# Pico_Audio_v0_10.net
KiCad netlist of a schematic drawn in EAGLE
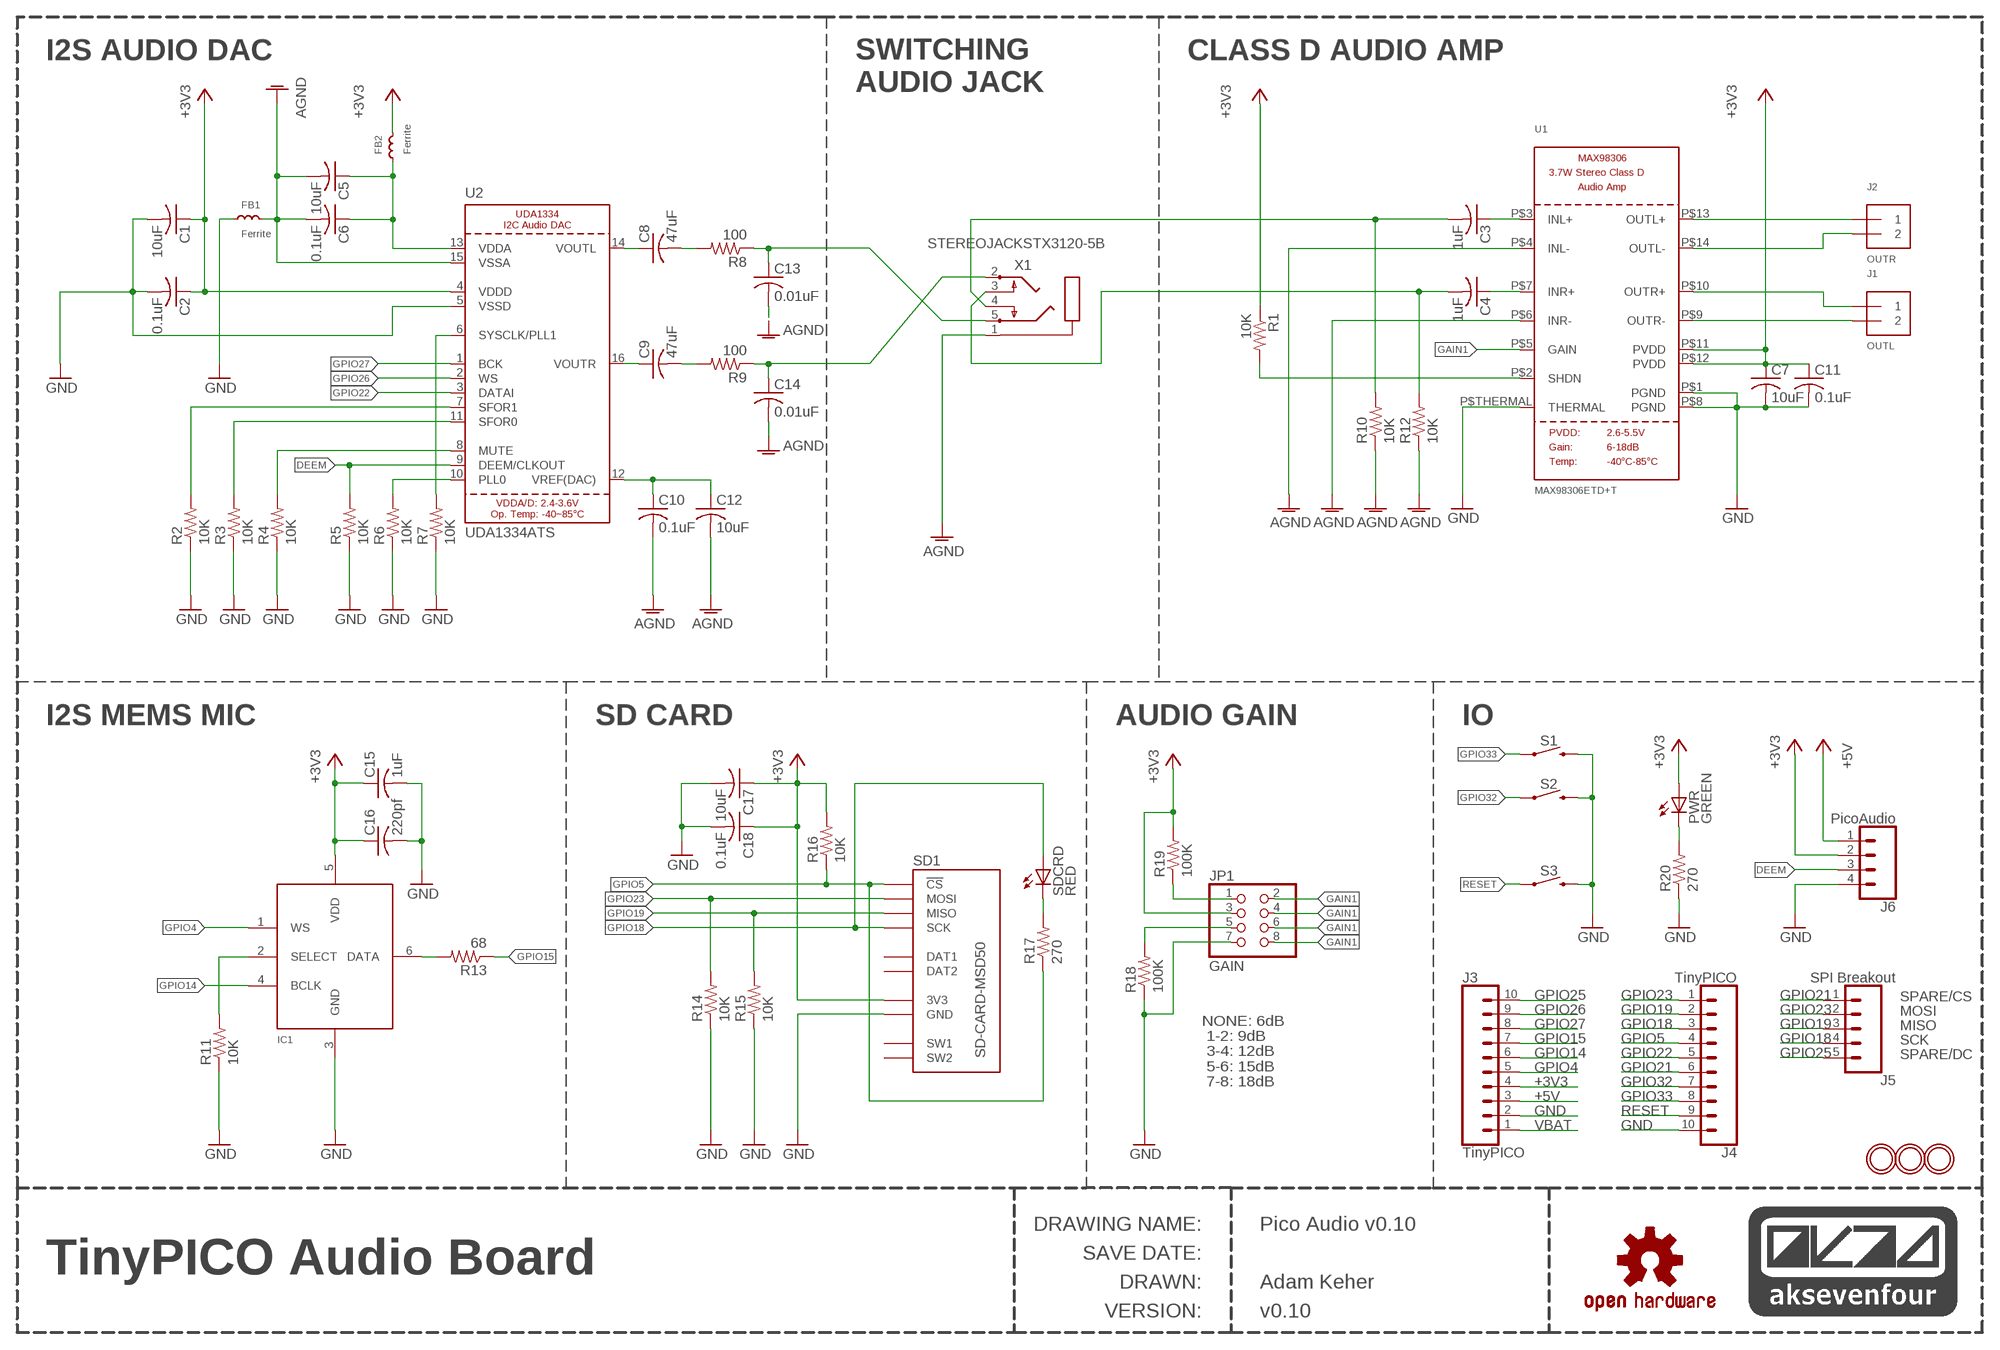
[diagram p0: schematic, sheet 1]

(export (version "E")
  (design (tool "Eeschema 10.0.6"))
  (components
    (comp (ref "AK74LOGO2")
      (value "AK74_LOGO")
      (footprint "eagle-import:AK74_LOGO_MEDIUM_TEXTONLY")
      (libsource (lib "eagle-import") (part "AK74_LOGO"))
    )
    (comp (ref "C1")
      (value "10uF")
      (footprint "eagle-import:C0603K")
      (libsource (lib "eagle-import") (part "C-USC0603K"))
    )
    (comp (ref "C2")
      (value "0.1uF")
      (footprint "eagle-import:C0402K")
      (libsource (lib "eagle-import") (part "C-USC0402K"))
    )
    (comp (ref "C3")
      (value "1uF")
      (footprint "eagle-import:C0402K")
      (libsource (lib "eagle-import") (part "C-USC0402K"))
    )
    (comp (ref "C4")
      (value "1uF")
      (footprint "eagle-import:C0402K")
      (libsource (lib "eagle-import") (part "C-USC0402K"))
    )
    (comp (ref "C5")
      (value "10uF")
      (footprint "eagle-import:C0603K")
      (libsource (lib "eagle-import") (part "C-USC0603K"))
    )
    (comp (ref "C6")
      (value "0.1uF")
      (footprint "eagle-import:C0402K")
      (libsource (lib "eagle-import") (part "C-USC0402K"))
    )
    (comp (ref "C7")
      (value "10uF")
      (footprint "eagle-import:C0603K")
      (libsource (lib "eagle-import") (part "C-USC0603K"))
    )
    (comp (ref "C8")
      (value "47uF")
      (footprint "eagle-import:C1210K")
      (libsource (lib "eagle-import") (part "C-USC1210K"))
    )
    (comp (ref "C9")
      (value "47uF")
      (footprint "eagle-import:C1210K")
      (libsource (lib "eagle-import") (part "C-USC1210K"))
    )
    (comp (ref "C10")
      (value "0.1uF")
      (footprint "eagle-import:C0402K")
      (libsource (lib "eagle-import") (part "C-USC0402K"))
    )
    (comp (ref "C11")
      (value "0.1uF")
      (footprint "eagle-import:C0402K")
      (libsource (lib "eagle-import") (part "C-USC0402K"))
    )
    (comp (ref "C12")
      (value "10uF")
      (footprint "eagle-import:C0603K")
      (libsource (lib "eagle-import") (part "C-USC0603K"))
    )
    (comp (ref "C13")
      (value "0.01uF")
      (footprint "eagle-import:C0402K")
      (libsource (lib "eagle-import") (part "C-USC0402K"))
    )
    (comp (ref "C14")
      (value "0.01uF")
      (footprint "eagle-import:C0402K")
      (libsource (lib "eagle-import") (part "C-USC0402K"))
    )
    (comp (ref "C15")
      (value "1uF")
      (footprint "eagle-import:C0402K")
      (libsource (lib "eagle-import") (part "C-USC0402K"))
    )
    (comp (ref "C16")
      (value "220pf")
      (footprint "eagle-import:C0402K")
      (libsource (lib "eagle-import") (part "C-USC0402K"))
    )
    (comp (ref "C17")
      (value "10uF")
      (footprint "eagle-import:C0603K")
      (libsource (lib "eagle-import") (part "C-USC0603K"))
    )
    (comp (ref "C18")
      (value "0.1uF")
      (footprint "eagle-import:C0402K")
      (libsource (lib "eagle-import") (part "C-USC0402K"))
    )
    (comp (ref "FB1")
      (value "Ferrite")
      (footprint "eagle-import:R0805")
      (libsource (lib "eagle-import") (part "FERRITEL0805"))
    )
    (comp (ref "FB2")
      (value "Ferrite")
      (footprint "eagle-import:R0805")
      (libsource (lib "eagle-import") (part "FERRITEL0805"))
    )
    (comp (ref "IC1")
      (value "MIC_I2S_SPH0645")
      (footprint "eagle-import:SPH0645LM4H")
      (libsource (lib "eagle-import") (part "MIC_I2S_SPH0645"))
    )
    (comp (ref "J1")
      (value "OUTL")
      (footprint "eagle-import:TERMBLOCK_1X2-3.5MM")
      (libsource (lib "eagle-import") (part "TERMBLOCK_1X2"))
    )
    (comp (ref "J2")
      (value "OUTR")
      (footprint "eagle-import:TERMBLOCK_1X2-3.5MM")
      (libsource (lib "eagle-import") (part "TERMBLOCK_1X2"))
    )
    (comp (ref "J3")
      (value "TinyPICO")
      (footprint "eagle-import:1X10_NO_SILK")
      (libsource (lib "eagle-import") (part "TINYPICO_HEADER_10NO_SILK_PTH_FEMALE"))
    )
    (comp (ref "J4")
      (value "TinyPICO")
      (footprint "eagle-import:1X10_NO_SILK")
      (libsource (lib "eagle-import") (part "TINYPICO_HEADER_10NO_SILK_PTH_FEMALE"))
    )
    (comp (ref "J5")
      (value "SPI Breakout")
      (footprint "eagle-import:1X05_NO_SILK")
      (libsource (lib "eagle-import") (part "CONN_05NO_SILK"))
    )
    (comp (ref "J6")
      (value "PicoAudio")
      (footprint "eagle-import:1X04_NO_SILK")
      (libsource (lib "eagle-import") (part "CONN_041X04_NO_SILK"))
    )
    (comp (ref "JP1")
      (value "GAIN")
      (footprint "eagle-import:2X04")
      (libsource (lib "eagle-import") (part "PINHD-2X4"))
    )
    (comp (ref "LOGO2")
      (value "OSHW-LOGOM")
      (footprint "eagle-import:OSHW-LOGO-M")
      (libsource (lib "eagle-import") (part "OSHW-LOGOM"))
    )
    (comp (ref "PWR")
      (value "GREEN")
      (footprint "eagle-import:CHIP-LED0805")
      (libsource (lib "eagle-import") (part "LEDCHIP-LED0805"))
    )
    (comp (ref "R1")
      (value "10K")
      (footprint "eagle-import:R0402")
      (libsource (lib "eagle-import") (part "R-US_R0402"))
    )
    (comp (ref "R2")
      (value "10K")
      (footprint "eagle-import:R0402")
      (libsource (lib "eagle-import") (part "R-US_R0402"))
    )
    (comp (ref "R3")
      (value "10K")
      (footprint "eagle-import:R0402")
      (libsource (lib "eagle-import") (part "R-US_R0402"))
    )
    (comp (ref "R4")
      (value "10K")
      (footprint "eagle-import:R0402")
      (libsource (lib "eagle-import") (part "R-US_R0402"))
    )
    (comp (ref "R5")
      (value "10K")
      (footprint "eagle-import:R0402")
      (libsource (lib "eagle-import") (part "R-US_R0402"))
    )
    (comp (ref "R6")
      (value "10K")
      (footprint "eagle-import:R0402")
      (libsource (lib "eagle-import") (part "R-US_R0402"))
    )
    (comp (ref "R7")
      (value "10K")
      (footprint "eagle-import:R0402")
      (libsource (lib "eagle-import") (part "R-US_R0402"))
    )
    (comp (ref "R8")
      (value "100")
      (footprint "eagle-import:R0402")
      (libsource (lib "eagle-import") (part "R-US_R0402"))
    )
    (comp (ref "R9")
      (value "100")
      (footprint "eagle-import:R0402")
      (libsource (lib "eagle-import") (part "R-US_R0402"))
    )
    (comp (ref "R10")
      (value "10K")
      (footprint "eagle-import:R0402")
      (libsource (lib "eagle-import") (part "R-US_R0402"))
    )
    (comp (ref "R11")
      (value "10K")
      (footprint "eagle-import:R0402")
      (libsource (lib "eagle-import") (part "R-US_R0402"))
    )
    (comp (ref "R12")
      (value "10K")
      (footprint "eagle-import:R0402")
      (libsource (lib "eagle-import") (part "R-US_R0402"))
    )
    (comp (ref "R13")
      (value "68")
      (footprint "eagle-import:R0402")
      (libsource (lib "eagle-import") (part "R-US_R0402"))
    )
    (comp (ref "R14")
      (value "10K")
      (footprint "eagle-import:R0402")
      (libsource (lib "eagle-import") (part "R-US_R0402"))
    )
    (comp (ref "R15")
      (value "10K")
      (footprint "eagle-import:R0402")
      (libsource (lib "eagle-import") (part "R-US_R0402"))
    )
    (comp (ref "R16")
      (value "10K")
      (footprint "eagle-import:R0402")
      (libsource (lib "eagle-import") (part "R-US_R0402"))
    )
    (comp (ref "R17")
      (value "270")
      (footprint "eagle-import:R0402")
      (libsource (lib "eagle-import") (part "R-US_R0402"))
    )
    (comp (ref "R18")
      (value "100K")
      (footprint "eagle-import:R0402")
      (libsource (lib "eagle-import") (part "R-US_R0402"))
    )
    (comp (ref "R19")
      (value "100K")
      (footprint "eagle-import:R0402")
      (libsource (lib "eagle-import") (part "R-US_R0402"))
    )
    (comp (ref "R20")
      (value "270")
      (footprint "eagle-import:R0402")
      (libsource (lib "eagle-import") (part "R-US_R0402"))
    )
    (comp (ref "S1")
      (value "MOMENTARY-SWITCH-SPST-SMD-4.6X2.8MM")
      (footprint "eagle-import:TACTILE_SWITCH_SMD_4.6X2.8MM")
      (libsource (lib "eagle-import") (part "MOMENTARY-SWITCH-SPST-SMD-4.6X2.8MM"))
    )
    (comp (ref "S2")
      (value "MOMENTARY-SWITCH-SPST-SMD-4.6X2.8MM")
      (footprint "eagle-import:TACTILE_SWITCH_SMD_4.6X2.8MM")
      (libsource (lib "eagle-import") (part "MOMENTARY-SWITCH-SPST-SMD-4.6X2.8MM"))
    )
    (comp (ref "S3")
      (value "MOMENTARY-SWITCH-SPST-SMD-4.6X2.8MM")
      (footprint "eagle-import:TACTILE_SWITCH_SMD_4.6X2.8MM")
      (libsource (lib "eagle-import") (part "MOMENTARY-SWITCH-SPST-SMD-4.6X2.8MM"))
    )
    (comp (ref "SD1")
      (value "SD-CARD-MSD50")
      (footprint "eagle-import:SD_5031821853")
      (libsource (lib "eagle-import") (part "SD-CARD-MSD50"))
    )
    (comp (ref "SDCRD")
      (value "RED")
      (footprint "eagle-import:CHIP-LED0805")
      (libsource (lib "eagle-import") (part "LEDCHIP-LED0805"))
    )
    (comp (ref "U$12")
      (value "MOUNTINGHOLE2.5")
      (footprint "eagle-import:MOUNTINGHOLE_2.5_PLATED")
      (libsource (lib "eagle-import") (part "MOUNTINGHOLE2.5"))
    )
    (comp (ref "U$13")
      (value "MOUNTINGHOLE2.5")
      (footprint "eagle-import:MOUNTINGHOLE_2.5_PLATED")
      (libsource (lib "eagle-import") (part "MOUNTINGHOLE2.5"))
    )
    (comp (ref "U$14")
      (value "MOUNTINGHOLE2.5")
      (footprint "eagle-import:MOUNTINGHOLE_2.5_PLATED")
      (libsource (lib "eagle-import") (part "MOUNTINGHOLE2.5"))
    )
    (comp (ref "U1")
      (value "MAX98306ETD+T")
      (footprint "eagle-import:TDFN14_3X3MM")
      (libsource (lib "eagle-import") (part "AUDIOAMP_MAX98306"))
    )
    (comp (ref "U2")
      (value "UDA1334ATS")
      (footprint "eagle-import:SSOP16_4.4MM")
      (libsource (lib "eagle-import") (part "AUDIO_I2S_UDA1334{dblquote}{dblquote}"))
    )
    (comp (ref "X1")
      (value "STEREOJACKSTX3120-5B")
      (footprint "eagle-import:STX3100")
      (libsource (lib "eagle-import") (part "STEREOJACKSTX3120-5B"))
    )
  )
  (nets
    (net (code "1") (name "+3V3") (class "Default")
      (node (ref "C1") (pin "1") (pinfunction "1_1") (pintype "passive"))
      (node (ref "C11") (pin "1") (pinfunction "1_1") (pintype "passive"))
      (node (ref "C15") (pin "1") (pinfunction "1_1") (pintype "passive"))
      (node (ref "C16") (pin "1") (pinfunction "1_1") (pintype "passive"))
      (node (ref "C17") (pin "1") (pinfunction "1_1") (pintype "passive"))
      (node (ref "C18") (pin "1") (pinfunction "1_1") (pintype "passive"))
      (node (ref "C2") (pin "1") (pinfunction "1_1") (pintype "passive"))
      (node (ref "C7") (pin "1") (pinfunction "1_1") (pintype "passive"))
      (node (ref "FB2") (pin "2") (pinfunction "2_2") (pintype "passive"))
      (node (ref "IC1") (pin "5") (pinfunction "VDD_5") (pintype "power_in"))
      (node (ref "J3") (pin "4") (pinfunction "4_4") (pintype "passive"))
      (node (ref "J6") (pin "2") (pinfunction "2_2") (pintype "passive"))
      (node (ref "JP1") (pin "3") (pinfunction "3_3") (pintype "passive"))
      (node (ref "PWR") (pin "A") (pinfunction "A_A") (pintype "passive"))
      (node (ref "R1") (pin "1") (pinfunction "1_1") (pintype "passive"))
      (node (ref "R16") (pin "2") (pinfunction "2_2") (pintype "passive"))
      (node (ref "R19") (pin "2") (pinfunction "2_2") (pintype "passive"))
      (node (ref "SD1") (pin "VCC") (pinfunction "3V3_VCC") (pintype "bidirectional"))
      (node (ref "U1") (pin "P$11") (pinfunction "PVDD_P$11") (pintype "power_in"))
      (node (ref "U1") (pin "P$12") (pinfunction "PVDD_P$12") (pintype "power_in"))
      (node (ref "U2") (pin "4") (pinfunction "VDDD_4") (pintype "power_in"))
    )
    (net (code "2") (name "+5V") (class "Default")
      (node (ref "J3") (pin "3") (pinfunction "3_3") (pintype "passive"))
      (node (ref "J6") (pin "1") (pinfunction "1_1") (pintype "passive"))
    )
    (net (code "3") (name "/GPIO21") (class "Default")
      (node (ref "J4") (pin "6") (pinfunction "6_6") (pintype "passive"))
      (node (ref "J5") (pin "1") (pinfunction "1_1") (pintype "passive"))
    )
    (net (code "4") (name "/GPIO25") (class "Default")
      (node (ref "J3") (pin "10") (pinfunction "10_10") (pintype "passive"))
      (node (ref "J5") (pin "5") (pinfunction "5_5") (pintype "passive"))
    )
    (net (code "5") (name "/VBAT") (class "Default")
      (node (ref "J3") (pin "1") (pinfunction "1_1") (pintype "passive"))
    )
    (net (code "6") (name "AGND") (class "Default")
      (node (ref "C10") (pin "2") (pinfunction "2_2") (pintype "passive"))
      (node (ref "C12") (pin "2") (pinfunction "2_2") (pintype "passive"))
      (node (ref "C13") (pin "2") (pinfunction "2_2") (pintype "passive"))
      (node (ref "C14") (pin "2") (pinfunction "2_2") (pintype "passive"))
      (node (ref "C5") (pin "2") (pinfunction "2_2") (pintype "passive"))
      (node (ref "C6") (pin "2") (pinfunction "2_2") (pintype "passive"))
      (node (ref "FB1") (pin "2") (pinfunction "2_2") (pintype "passive"))
      (node (ref "R10") (pin "1") (pinfunction "1_1") (pintype "passive"))
      (node (ref "R12") (pin "1") (pinfunction "1_1") (pintype "passive"))
      (node (ref "U1") (pin "P$4") (pinfunction "INL-_P$4") (pintype "input"))
      (node (ref "U1") (pin "P$6") (pinfunction "INR-_P$6") (pintype "input"))
      (node (ref "U2") (pin "15") (pinfunction "VSSA_15") (pintype "power_in"))
      (node (ref "X1") (pin "1") (pinfunction "1_1") (pintype "passive"))
    )
    (net (code "7") (name "DEEM") (class "Default")
      (node (ref "J6") (pin "3") (pinfunction "3_3") (pintype "passive"))
      (node (ref "R5") (pin "2") (pinfunction "2_2") (pintype "passive"))
      (node (ref "U2") (pin "9") (pinfunction "DEEM/CLKOUT_9") (pintype "bidirectional"))
    )
    (net (code "8") (name "GAIN1") (class "Default")
      (node (ref "JP1") (pin "2") (pinfunction "2_2") (pintype "passive"))
      (node (ref "JP1") (pin "4") (pinfunction "4_4") (pintype "passive"))
      (node (ref "JP1") (pin "6") (pinfunction "6_6") (pintype "passive"))
      (node (ref "JP1") (pin "8") (pinfunction "8_8") (pintype "passive"))
      (node (ref "U1") (pin "P$5") (pinfunction "GAIN_P$5") (pintype "input"))
    )
    (net (code "9") (name "GND") (class "Default")
      (node (ref "C1") (pin "2") (pinfunction "2_2") (pintype "passive"))
      (node (ref "C11") (pin "2") (pinfunction "2_2") (pintype "passive"))
      (node (ref "C15") (pin "2") (pinfunction "2_2") (pintype "passive"))
      (node (ref "C16") (pin "2") (pinfunction "2_2") (pintype "passive"))
      (node (ref "C17") (pin "2") (pinfunction "2_2") (pintype "passive"))
      (node (ref "C18") (pin "2") (pinfunction "2_2") (pintype "passive"))
      (node (ref "C2") (pin "2") (pinfunction "2_2") (pintype "passive"))
      (node (ref "C7") (pin "2") (pinfunction "2_2") (pintype "passive"))
      (node (ref "FB1") (pin "1") (pinfunction "1_1") (pintype "passive"))
      (node (ref "IC1") (pin "3") (pinfunction "GND_3") (pintype "power_in"))
      (node (ref "J3") (pin "2") (pinfunction "2_2") (pintype "passive"))
      (node (ref "J4") (pin "10") (pinfunction "10_10") (pintype "passive"))
      (node (ref "J6") (pin "4") (pinfunction "4_4") (pintype "passive"))
      (node (ref "JP1") (pin "7") (pinfunction "7_7") (pintype "passive"))
      (node (ref "R11") (pin "1") (pinfunction "1_1") (pintype "passive"))
      (node (ref "R14") (pin "1") (pinfunction "1_1") (pintype "passive"))
      (node (ref "R15") (pin "1") (pinfunction "1_1") (pintype "passive"))
      (node (ref "R18") (pin "1") (pinfunction "1_1") (pintype "passive"))
      (node (ref "R2") (pin "1") (pinfunction "1_1") (pintype "passive"))
      (node (ref "R20") (pin "1") (pinfunction "1_1") (pintype "passive"))
      (node (ref "R3") (pin "1") (pinfunction "1_1") (pintype "passive"))
      (node (ref "R4") (pin "1") (pinfunction "1_1") (pintype "passive"))
      (node (ref "R5") (pin "1") (pinfunction "1_1") (pintype "passive"))
      (node (ref "R6") (pin "1") (pinfunction "1_1") (pintype "passive"))
      (node (ref "R7") (pin "1") (pinfunction "1_1") (pintype "passive"))
      (node (ref "S1") (pin "3") (pinfunction "2_3") (pintype "passive"))
      (node (ref "S1") (pin "4") (pinfunction "2_4") (pintype "passive"))
      (node (ref "S2") (pin "3") (pinfunction "2_3") (pintype "passive"))
      (node (ref "S2") (pin "4") (pinfunction "2_4") (pintype "passive"))
      (node (ref "S3") (pin "3") (pinfunction "2_3") (pintype "passive"))
      (node (ref "S3") (pin "4") (pinfunction "2_4") (pintype "passive"))
      (node (ref "SD1") (pin "GND") (pinfunction "GND_GND") (pintype "bidirectional"))
      (node (ref "U1") (pin "P$1") (pinfunction "PGND_P$1") (pintype "power_in"))
      (node (ref "U1") (pin "P$8") (pinfunction "PGND_P$8") (pintype "power_in"))
      (node (ref "U1") (pin "P$THERMAL") (pinfunction "THERMAL_P$THERMAL") (pintype "power_in"))
      (node (ref "U2") (pin "5") (pinfunction "VSSD_5") (pintype "power_in"))
    )
    (net (code "10") (name "GPIO4") (class "Default")
      (node (ref "IC1") (pin "1") (pinfunction "WS_1") (pintype "input"))
      (node (ref "J3") (pin "5") (pinfunction "5_5") (pintype "passive"))
    )
    (net (code "11") (name "GPIO5") (class "Default")
      (node (ref "J4") (pin "4") (pinfunction "4_4") (pintype "passive"))
      (node (ref "R16") (pin "1") (pinfunction "1_1") (pintype "passive"))
      (node (ref "R17") (pin "1") (pinfunction "1_1") (pintype "passive"))
      (node (ref "SD1") (pin "CS") (pinfunction "~{CS}_CS") (pintype "bidirectional"))
    )
    (net (code "12") (name "GPIO14") (class "Default")
      (node (ref "IC1") (pin "4") (pinfunction "BCLK_4") (pintype "input"))
      (node (ref "J3") (pin "6") (pinfunction "6_6") (pintype "passive"))
    )
    (net (code "13") (name "GPIO15") (class "Default")
      (node (ref "J3") (pin "7") (pinfunction "7_7") (pintype "passive"))
      (node (ref "R13") (pin "1") (pinfunction "1_1") (pintype "passive"))
    )
    (net (code "14") (name "GPIO18") (class "Default")
      (node (ref "J4") (pin "3") (pinfunction "3_3") (pintype "passive"))
      (node (ref "J5") (pin "4") (pinfunction "4_4") (pintype "passive"))
      (node (ref "SD1") (pin "SCK") (pinfunction "SCK_SCK") (pintype "bidirectional"))
      (node (ref "SDCRD") (pin "A") (pinfunction "A_A") (pintype "passive"))
    )
    (net (code "15") (name "GPIO19") (class "Default")
      (node (ref "J4") (pin "2") (pinfunction "2_2") (pintype "passive"))
      (node (ref "J5") (pin "3") (pinfunction "3_3") (pintype "passive"))
      (node (ref "R15") (pin "2") (pinfunction "2_2") (pintype "passive"))
      (node (ref "SD1") (pin "MISO") (pinfunction "MISO_MISO") (pintype "bidirectional"))
    )
    (net (code "16") (name "GPIO22") (class "Default")
      (node (ref "J4") (pin "5") (pinfunction "5_5") (pintype "passive"))
      (node (ref "U2") (pin "3") (pinfunction "DATAI_3") (pintype "input"))
    )
    (net (code "17") (name "GPIO23") (class "Default")
      (node (ref "J4") (pin "1") (pinfunction "1_1") (pintype "passive"))
      (node (ref "J5") (pin "2") (pinfunction "2_2") (pintype "passive"))
      (node (ref "R14") (pin "2") (pinfunction "2_2") (pintype "passive"))
      (node (ref "SD1") (pin "MOSI") (pinfunction "MOSI_MOSI") (pintype "bidirectional"))
    )
    (net (code "18") (name "GPIO26") (class "Default")
      (node (ref "J3") (pin "9") (pinfunction "9_9") (pintype "passive"))
      (node (ref "U2") (pin "2") (pinfunction "WS_2") (pintype "input"))
    )
    (net (code "19") (name "GPIO27") (class "Default")
      (node (ref "J3") (pin "8") (pinfunction "8_8") (pintype "passive"))
      (node (ref "U2") (pin "1") (pinfunction "BCK_1") (pintype "input"))
    )
    (net (code "20") (name "GPIO32") (class "Default")
      (node (ref "J4") (pin "7") (pinfunction "7_7") (pintype "passive"))
      (node (ref "S2") (pin "1") (pinfunction "1_1") (pintype "passive"))
      (node (ref "S2") (pin "2") (pinfunction "1_2") (pintype "passive"))
    )
    (net (code "21") (name "GPIO33") (class "Default")
      (node (ref "J4") (pin "8") (pinfunction "8_8") (pintype "passive"))
      (node (ref "S1") (pin "1") (pinfunction "1_1") (pintype "passive"))
      (node (ref "S1") (pin "2") (pinfunction "1_2") (pintype "passive"))
    )
    (net (code "22") (name "Net-(C3-Pad2)") (class "Default")
      (node (ref "C3") (pin "2") (pinfunction "2_2") (pintype "passive"))
      (node (ref "R10") (pin "2") (pinfunction "2_2") (pintype "passive"))
      (node (ref "X1") (pin "4") (pinfunction "4_4") (pintype "passive"))
    )
    (net (code "23") (name "Net-(C4-Pad2)") (class "Default")
      (node (ref "C4") (pin "2") (pinfunction "2_2") (pintype "passive"))
      (node (ref "R12") (pin "2") (pinfunction "2_2") (pintype "passive"))
      (node (ref "X1") (pin "3") (pinfunction "3_3") (pintype "passive"))
    )
    (net (code "24") (name "Net-(C8-Pad2)") (class "Default")
      (node (ref "C8") (pin "2") (pinfunction "2_2") (pintype "passive"))
      (node (ref "R8") (pin "2") (pinfunction "2_2") (pintype "passive"))
    )
    (net (code "25") (name "Net-(C9-Pad2)") (class "Default")
      (node (ref "C9") (pin "2") (pinfunction "2_2") (pintype "passive"))
      (node (ref "R9") (pin "2") (pinfunction "2_2") (pintype "passive"))
    )
    (net (code "26") (name "Net-(C13-Pad1)") (class "Default")
      (node (ref "C13") (pin "1") (pinfunction "1_1") (pintype "passive"))
      (node (ref "R8") (pin "1") (pinfunction "1_1") (pintype "passive"))
      (node (ref "X1") (pin "5") (pinfunction "5_5") (pintype "passive"))
    )
    (net (code "27") (name "Net-(C14-Pad1)") (class "Default")
      (node (ref "C14") (pin "1") (pinfunction "1_1") (pintype "passive"))
      (node (ref "R9") (pin "1") (pinfunction "1_1") (pintype "passive"))
      (node (ref "X1") (pin "2") (pinfunction "2_2") (pintype "passive"))
    )
    (net (code "28") (name "Net-(IC1-DATA)") (class "Default")
      (node (ref "IC1") (pin "6") (pinfunction "DATA_6") (pintype "output"))
      (node (ref "R13") (pin "2") (pinfunction "2_2") (pintype "passive"))
    )
    (net (code "29") (name "Net-(IC1-SELECT)") (class "Default")
      (node (ref "IC1") (pin "2") (pinfunction "SELECT_2") (pintype "input"))
      (node (ref "R11") (pin "2") (pinfunction "2_2") (pintype "passive"))
    )
    (net (code "30") (name "Net-(JP1-Pad1)") (class "Default")
      (node (ref "JP1") (pin "1") (pinfunction "1_1") (pintype "passive"))
      (node (ref "R19") (pin "1") (pinfunction "1_1") (pintype "passive"))
    )
    (net (code "31") (name "Net-(JP1-Pad5)") (class "Default")
      (node (ref "JP1") (pin "5") (pinfunction "5_5") (pintype "passive"))
      (node (ref "R18") (pin "2") (pinfunction "2_2") (pintype "passive"))
    )
    (net (code "32") (name "Net-(PWR-PadC)") (class "Default")
      (node (ref "PWR") (pin "C") (pinfunction "C_C") (pintype "passive"))
      (node (ref "R20") (pin "2") (pinfunction "2_2") (pintype "passive"))
    )
    (net (code "33") (name "Net-(R17-Pad2)") (class "Default")
      (node (ref "R17") (pin "2") (pinfunction "2_2") (pintype "passive"))
      (node (ref "SDCRD") (pin "C") (pinfunction "C_C") (pintype "passive"))
    )
    (net (code "34") (name "Net-(U1-INL+)") (class "Default")
      (node (ref "C3") (pin "1") (pinfunction "1_1") (pintype "passive"))
      (node (ref "U1") (pin "P$3") (pinfunction "INL+_P$3") (pintype "input"))
    )
    (net (code "35") (name "Net-(U1-INR+)") (class "Default")
      (node (ref "C4") (pin "1") (pinfunction "1_1") (pintype "passive"))
      (node (ref "U1") (pin "P$7") (pinfunction "INR+_P$7") (pintype "input"))
    )
    (net (code "36") (name "Net-(U1-OUTL+)") (class "Default")
      (node (ref "J2") (pin "1") (pinfunction "1_1") (pintype "passive"))
      (node (ref "U1") (pin "P$13") (pinfunction "OUTL+_P$13") (pintype "output"))
    )
    (net (code "37") (name "Net-(U1-OUTL-)") (class "Default")
      (node (ref "J2") (pin "2") (pinfunction "2_2") (pintype "passive"))
      (node (ref "U1") (pin "P$14") (pinfunction "OUTL-_P$14") (pintype "output"))
    )
    (net (code "38") (name "Net-(U1-OUTR+)") (class "Default")
      (node (ref "J1") (pin "1") (pinfunction "1_1") (pintype "passive"))
      (node (ref "U1") (pin "P$10") (pinfunction "OUTR+_P$10") (pintype "output"))
    )
    (net (code "39") (name "Net-(U1-OUTR-)") (class "Default")
      (node (ref "J1") (pin "2") (pinfunction "2_2") (pintype "passive"))
      (node (ref "U1") (pin "P$9") (pinfunction "OUTR-_P$9") (pintype "output"))
    )
    (net (code "40") (name "Net-(U1-SHDN)") (class "Default")
      (node (ref "R1") (pin "2") (pinfunction "2_2") (pintype "passive"))
      (node (ref "U1") (pin "P$2") (pinfunction "SHDN_P$2") (pintype "input"))
    )
    (net (code "41") (name "Net-(U2-MUTE)") (class "Default")
      (node (ref "R4") (pin "2") (pinfunction "2_2") (pintype "passive"))
      (node (ref "U2") (pin "8") (pinfunction "MUTE_8") (pintype "input"))
    )
    (net (code "42") (name "Net-(U2-PLL0)") (class "Default")
      (node (ref "R6") (pin "2") (pinfunction "2_2") (pintype "passive"))
      (node (ref "U2") (pin "10") (pinfunction "PLL0_10") (pintype "input"))
    )
    (net (code "43") (name "Net-(U2-SFOR0)") (class "Default")
      (node (ref "R3") (pin "2") (pinfunction "2_2") (pintype "passive"))
      (node (ref "U2") (pin "11") (pinfunction "SFOR0_11") (pintype "input"))
    )
    (net (code "44") (name "Net-(U2-SFOR1)") (class "Default")
      (node (ref "R2") (pin "2") (pinfunction "2_2") (pintype "passive"))
      (node (ref "U2") (pin "7") (pinfunction "SFOR1_7") (pintype "input"))
    )
    (net (code "45") (name "Net-(U2-SYSCLK{slash}PLL1)") (class "Default")
      (node (ref "R7") (pin "2") (pinfunction "2_2") (pintype "passive"))
      (node (ref "U2") (pin "6") (pinfunction "SYSCLK/PLL1_6") (pintype "input"))
    )
    (net (code "46") (name "Net-(U2-VDDA)") (class "Default")
      (node (ref "C5") (pin "1") (pinfunction "1_1") (pintype "passive"))
      (node (ref "C6") (pin "1") (pinfunction "1_1") (pintype "passive"))
      (node (ref "FB2") (pin "1") (pinfunction "1_1") (pintype "passive"))
      (node (ref "U2") (pin "13") (pinfunction "VDDA_13") (pintype "power_in"))
    )
    (net (code "47") (name "Net-(U2-VOUTL)") (class "Default")
      (node (ref "C8") (pin "1") (pinfunction "1_1") (pintype "passive"))
      (node (ref "U2") (pin "14") (pinfunction "VOUTL_14") (pintype "output"))
    )
    (net (code "48") (name "Net-(U2-VOUTR)") (class "Default")
      (node (ref "C9") (pin "1") (pinfunction "1_1") (pintype "passive"))
      (node (ref "U2") (pin "16") (pinfunction "VOUTR_16") (pintype "output"))
    )
    (net (code "49") (name "Net-(U2-VREF(DAC))") (class "Default")
      (node (ref "C10") (pin "1") (pinfunction "1_1") (pintype "passive"))
      (node (ref "C12") (pin "1") (pinfunction "1_1") (pintype "passive"))
      (node (ref "U2") (pin "12") (pinfunction "VREF(DAC)_12") (pintype "output"))
    )
    (net (code "50") (name "RESET") (class "Default")
      (node (ref "J4") (pin "9") (pinfunction "9_9") (pintype "passive"))
      (node (ref "S3") (pin "1") (pinfunction "1_1") (pintype "passive"))
      (node (ref "S3") (pin "2") (pinfunction "1_2") (pintype "passive"))
    )
    (net (code "51") (name "unconnected-(SD1-PadDAT1)") (class "Default")
      (node (ref "SD1") (pin "DAT1") (pinfunction "DAT1_DAT1") (pintype "bidirectional"))
    )
    (net (code "52") (name "unconnected-(SD1-PadDAT2)") (class "Default")
      (node (ref "SD1") (pin "DAT2") (pinfunction "DAT2_DAT2") (pintype "bidirectional"))
    )
    (net (code "53") (name "unconnected-(SD1-PadSW1)") (class "Default")
      (node (ref "SD1") (pin "SW1") (pinfunction "SW1_SW1") (pintype "bidirectional"))
    )
    (net (code "54") (name "unconnected-(SD1-PadSW2)") (class "Default")
      (node (ref "SD1") (pin "SW2") (pinfunction "SW2_SW2") (pintype "bidirectional"))
    )
  )
)
